# 3310.net
KiCad netlist of a schematic drawn in EAGLE
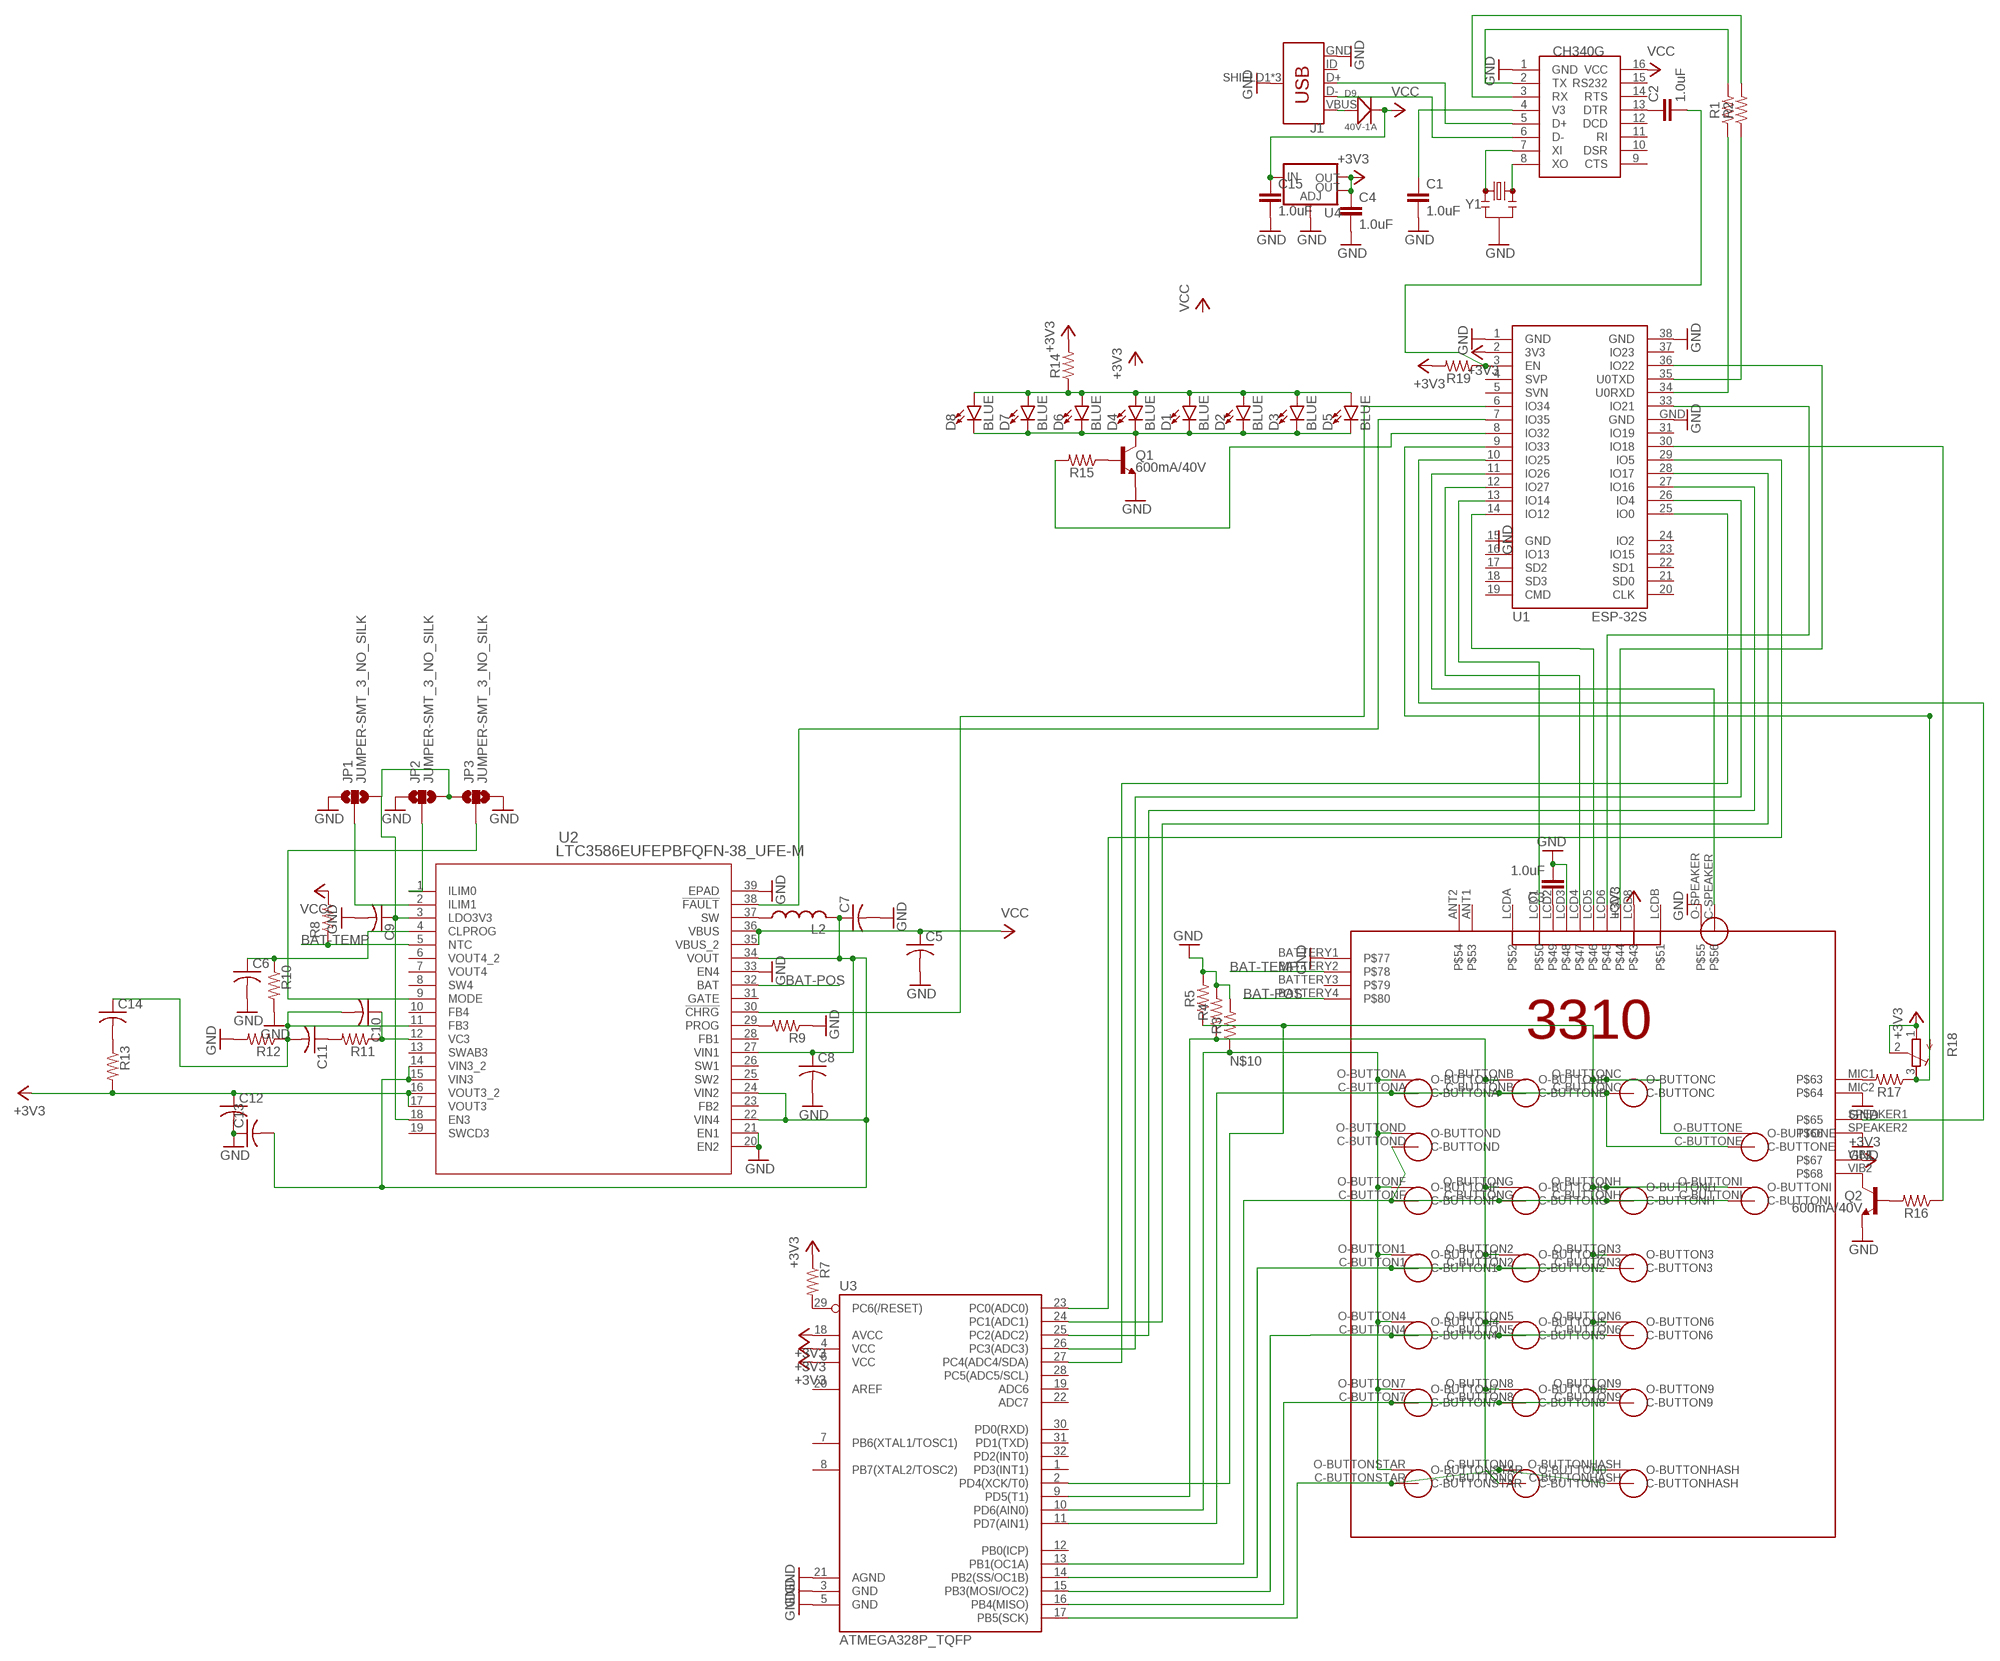
[diagram p0: schematic, sheet 1]

(export (version "E")
  (design (tool "Eeschema 10.0.6"))
  (components
    (comp (ref "C1")
      (value "1.0uF")
      (footprint "eagle-import:0805")
      (libsource (lib "eagle-import") (part "1.0UF-0805-25V-10%"))
    )
    (comp (ref "C2")
      (value "1.0uF")
      (footprint "eagle-import:0805")
      (libsource (lib "eagle-import") (part "1.0UF-0805-25V-10%"))
    )
    (comp (ref "C3")
      (value "1.0uF")
      (footprint "eagle-import:0805")
      (libsource (lib "eagle-import") (part "1.0UF-0805-25V-10%"))
    )
    (comp (ref "C4")
      (value "1.0uF")
      (footprint "eagle-import:0805")
      (libsource (lib "eagle-import") (part "1.0UF-0805-25V-10%"))
    )
    (comp (ref "C5")
      (value "C-USC0805K")
      (footprint "eagle-import:C0805K")
      (libsource (lib "eagle-import") (part "C-USC0805K"))
    )
    (comp (ref "C6")
      (value "C-USC0805K")
      (footprint "eagle-import:C0805K")
      (libsource (lib "eagle-import") (part "C-USC0805K"))
    )
    (comp (ref "C7")
      (value "C-USC0805K")
      (footprint "eagle-import:C0805K")
      (libsource (lib "eagle-import") (part "C-USC0805K"))
    )
    (comp (ref "C8")
      (value "C-USC0805K")
      (footprint "eagle-import:C0805K")
      (libsource (lib "eagle-import") (part "C-USC0805K"))
    )
    (comp (ref "C9")
      (value "C-USC0805K")
      (footprint "eagle-import:C0805K")
      (libsource (lib "eagle-import") (part "C-USC0805K"))
    )
    (comp (ref "C10")
      (value "C-USC0805K")
      (footprint "eagle-import:C0805K")
      (libsource (lib "eagle-import") (part "C-USC0805K"))
    )
    (comp (ref "C11")
      (value "C-USC0805K")
      (footprint "eagle-import:C0805K")
      (libsource (lib "eagle-import") (part "C-USC0805K"))
    )
    (comp (ref "C12")
      (value "C-USC0805K")
      (footprint "eagle-import:C0805K")
      (libsource (lib "eagle-import") (part "C-USC0805K"))
    )
    (comp (ref "C13")
      (value "C-USC0805K")
      (footprint "eagle-import:C0805K")
      (libsource (lib "eagle-import") (part "C-USC0805K"))
    )
    (comp (ref "C14")
      (value "C-USC0805K")
      (footprint "eagle-import:C0805K")
      (libsource (lib "eagle-import") (part "C-USC0805K"))
    )
    (comp (ref "C15")
      (value "1.0uF")
      (footprint "eagle-import:0805")
      (libsource (lib "eagle-import") (part "1.0UF-0805-25V-10%"))
    )
    (comp (ref "D1")
      (value "BLUE")
      (footprint "eagle-import:LED-1206")
      (libsource (lib "eagle-import") (part "LED-BLUE1206"))
    )
    (comp (ref "D2")
      (value "BLUE")
      (footprint "eagle-import:LED-1206")
      (libsource (lib "eagle-import") (part "LED-BLUE1206"))
    )
    (comp (ref "D3")
      (value "BLUE")
      (footprint "eagle-import:LED-1206")
      (libsource (lib "eagle-import") (part "LED-BLUE1206"))
    )
    (comp (ref "D4")
      (value "BLUE")
      (footprint "eagle-import:LED-1206")
      (libsource (lib "eagle-import") (part "LED-BLUE1206"))
    )
    (comp (ref "D5")
      (value "BLUE")
      (footprint "eagle-import:LED-1206")
      (libsource (lib "eagle-import") (part "LED-BLUE1206"))
    )
    (comp (ref "D6")
      (value "BLUE")
      (footprint "eagle-import:LED-1206")
      (libsource (lib "eagle-import") (part "LED-BLUE1206"))
    )
    (comp (ref "D7")
      (value "BLUE")
      (footprint "eagle-import:LED-1206")
      (libsource (lib "eagle-import") (part "LED-BLUE1206"))
    )
    (comp (ref "D8")
      (value "BLUE")
      (footprint "eagle-import:LED-1206")
      (libsource (lib "eagle-import") (part "LED-BLUE1206"))
    )
    (comp (ref "D9")
      (value "40V-1A")
      (footprint "eagle-import:DO-214AC")
      (fields (field (name "MPN") "1N5819"))
      (libsource (lib "eagle-import") (part "SMD-DIODE-SCHOTTKY-40V-1A(DO-214AC)"))
    )
    (comp (ref "J1")
      (value "USB_MICRO-BREDUCED_PASTE")
      (footprint "eagle-import:USB-B-MICRO-SMD_RED_PASTE")
      (libsource (lib "eagle-import") (part "USB_MICRO-BREDUCED_PASTE"))
    )
    (comp (ref "JP1")
      (value "JUMPER-SMT_3_NO_SILK")
      (footprint "eagle-import:SMT-JUMPER_3_NO_SILK")
      (libsource (lib "eagle-import") (part "JUMPER-SMT_3_NO_SILK"))
    )
    (comp (ref "JP2")
      (value "JUMPER-SMT_3_NO_SILK")
      (footprint "eagle-import:SMT-JUMPER_3_NO_SILK")
      (libsource (lib "eagle-import") (part "JUMPER-SMT_3_NO_SILK"))
    )
    (comp (ref "JP3")
      (value "JUMPER-SMT_3_NO_SILK")
      (footprint "eagle-import:SMT-JUMPER_3_NO_SILK")
      (libsource (lib "eagle-import") (part "JUMPER-SMT_3_NO_SILK"))
    )
    (comp (ref "L2")
      (value "L-USL3216C")
      (footprint "eagle-import:L3216C")
      (libsource (lib "eagle-import") (part "L-USL3216C"))
    )
    (comp (ref "Q1")
      (value "600mA/40V")
      (footprint "eagle-import:SOT23-3")
      (libsource (lib "eagle-import") (part "TRANS_NPN-MMBT2222AL"))
    )
    (comp (ref "Q2")
      (value "600mA/40V")
      (footprint "eagle-import:SOT23-3")
      (libsource (lib "eagle-import") (part "TRANS_NPN-MMBT2222AL"))
    )
    (comp (ref "R1")
      (value "RESISTOR0805")
      (footprint "eagle-import:0805")
      (libsource (lib "eagle-import") (part "RESISTOR0805"))
    )
    (comp (ref "R2")
      (value "RESISTOR0805")
      (footprint "eagle-import:0805")
      (libsource (lib "eagle-import") (part "RESISTOR0805"))
    )
    (comp (ref "R3")
      (value "RESISTOR0805")
      (footprint "eagle-import:0805")
      (libsource (lib "eagle-import") (part "RESISTOR0805"))
    )
    (comp (ref "R4")
      (value "RESISTOR0805")
      (footprint "eagle-import:0805")
      (libsource (lib "eagle-import") (part "RESISTOR0805"))
    )
    (comp (ref "R5")
      (value "RESISTOR0805")
      (footprint "eagle-import:0805")
      (libsource (lib "eagle-import") (part "RESISTOR0805"))
    )
    (comp (ref "R7")
      (value "R-US_R0805")
      (footprint "eagle-import:R0805")
      (libsource (lib "eagle-import") (part "R-US_R0805"))
    )
    (comp (ref "R8")
      (value "R-US_R0805")
      (footprint "eagle-import:R0805")
      (libsource (lib "eagle-import") (part "R-US_R0805"))
    )
    (comp (ref "R9")
      (value "R-US_R0805")
      (footprint "eagle-import:R0805")
      (libsource (lib "eagle-import") (part "R-US_R0805"))
    )
    (comp (ref "R10")
      (value "R-US_R0805")
      (footprint "eagle-import:R0805")
      (libsource (lib "eagle-import") (part "R-US_R0805"))
    )
    (comp (ref "R11")
      (value "R-US_R0805")
      (footprint "eagle-import:R0805")
      (libsource (lib "eagle-import") (part "R-US_R0805"))
    )
    (comp (ref "R12")
      (value "R-US_R0805")
      (footprint "eagle-import:R0805")
      (libsource (lib "eagle-import") (part "R-US_R0805"))
    )
    (comp (ref "R13")
      (value "R-US_R0805")
      (footprint "eagle-import:R0805")
      (libsource (lib "eagle-import") (part "R-US_R0805"))
    )
    (comp (ref "R14")
      (value "RESISTOR0805")
      (footprint "eagle-import:0805")
      (libsource (lib "eagle-import") (part "RESISTOR0805"))
    )
    (comp (ref "R15")
      (value "RESISTOR0805")
      (footprint "eagle-import:0805")
      (libsource (lib "eagle-import") (part "RESISTOR0805"))
    )
    (comp (ref "R16")
      (value "RESISTOR0805")
      (footprint "eagle-import:0805")
      (libsource (lib "eagle-import") (part "RESISTOR0805"))
    )
    (comp (ref "R17")
      (value "RESISTOR0805")
      (footprint "eagle-import:0805")
      (libsource (lib "eagle-import") (part "RESISTOR0805"))
    )
    (comp (ref "R18")
      (value "R-TRIMM3103")
      (footprint "eagle-import:RTRIM3103")
      (libsource (lib "eagle-import") (part "R-TRIMM3103"))
    )
    (comp (ref "R19")
      (value "RESISTOR0805")
      (footprint "eagle-import:0805")
      (libsource (lib "eagle-import") (part "RESISTOR0805"))
    )
    (comp (ref "U$1")
      (value "3310NOJACKANDSIM")
      (footprint "eagle-import:3310NOJACKANDSIM")
      (libsource (lib "eagle-import") (part "3310NOJACKANDSIM"))
    )
    (comp (ref "U$2")
      (value "CH340G")
      (footprint "eagle-import:SOIC16")
      (libsource (lib "eagle-import") (part "CH340G"))
    )
    (comp (ref "U1")
      (value "ESP-32S")
      (footprint "eagle-import:ESP-32S")
      (libsource (lib "eagle-import") (part "ESP-32S"))
    )
    (comp (ref "U2")
      (value "LTC3586EUFEPBFQFN-38_UFE-M")
      (footprint "eagle-import:QFN-38_UFE-M")
      (fields (field (name "MANUFACTURER_PART_NUMBER") "LTC3586EUFE#PBF"))
      (libsource (lib "eagle-import") (part "LTC3586EUFEPBFQFN-38_UFE-M"))
    )
    (comp (ref "U3")
      (value "ATMEGA328P_TQFP")
      (footprint "eagle-import:TQFP32-08")
      (libsource (lib "eagle-import") (part "ATMEGA328P_TQFP"))
    )
    (comp (ref "U4")
      (value "V_REG_LM1117SOT223")
      (footprint "eagle-import:SOT223")
      (libsource (lib "eagle-import") (part "V_REG_LM1117SOT223"))
    )
    (comp (ref "Y1")
      (value "RESONATORSMD-3.2X1.3")
      (footprint "eagle-import:RESONATOR-SMD-3.2X1.3")
      (libsource (lib "eagle-import") (part "RESONATORSMD-3.2X1.3"))
    )
  )
  (nets
    (net (code "1") (name "+3V3") (class "Default")
      (node (ref "C12") (pin "1") (pinfunction "1_1") (pintype "passive"))
      (node (ref "C4") (pin "1") (pinfunction "1_1") (pintype "passive"))
      (node (ref "R13") (pin "2") (pinfunction "2_2") (pintype "passive"))
      (node (ref "R14") (pin "2") (pinfunction "2_2") (pintype "passive"))
      (node (ref "R18") (pin "1") (pinfunction "A_1") (pintype "passive"))
      (node (ref "R18") (pin "2") (pinfunction "S_2") (pintype "passive"))
      (node (ref "R19") (pin "2") (pinfunction "2_2") (pintype "passive"))
      (node (ref "R7") (pin "1") (pinfunction "1_1") (pintype "passive"))
      (node (ref "U$1") (pin "LCD8") (pinfunction "P$43_LCD8") (pintype "bidirectional"))
      (node (ref "U$1") (pin "VIB1") (pinfunction "P$67_VIB1") (pintype "bidirectional"))
      (node (ref "U1") (pin "2") (pinfunction "3V3_2") (pintype "power_in"))
      (node (ref "U2") (pin "16") (pinfunction "VOUT3_2_16") (pintype "output"))
      (node (ref "U2") (pin "17") (pinfunction "VOUT3_17") (pintype "output"))
      (node (ref "U3") (pin "18") (pinfunction "AVCC_18") (pintype "bidirectional"))
      (node (ref "U3") (pin "4") (pinfunction "VCC_4") (pintype "bidirectional"))
      (node (ref "U3") (pin "6") (pinfunction "VCC_6") (pintype "bidirectional"))
      (node (ref "U4") (pin "2") (pinfunction "OUT_2") (pintype "output"))
      (node (ref "U4") (pin "4") (pinfunction "OUT_4") (pintype "output"))
    )
    (net (code "2") (name "/BAT-POS") (class "Default")
      (node (ref "U$1") (pin "BATTERY4") (pinfunction "P$80_BATTERY4") (pintype "bidirectional"))
      (node (ref "U2") (pin "32") (pinfunction "BAT_32") (pintype "passive"))
    )
    (net (code "3") (name "/BAT-TEMP") (class "Default")
      (node (ref "R8") (pin "1") (pinfunction "1_1") (pintype "passive"))
      (node (ref "U$1") (pin "BATTERY2") (pinfunction "P$78_BATTERY2") (pintype "bidirectional"))
      (node (ref "U2") (pin "5") (pinfunction "NTC_5") (pintype "input"))
    )
    (net (code "4") (name "/N$10") (class "Default")
      (node (ref "R3") (pin "1") (pinfunction "1_1") (pintype "passive"))
      (node (ref "U$1") (pin "O-BUTTON1") (pinfunction "O-BUTTON1_O-BUTTON1") (pintype "bidirectional"))
      (node (ref "U$1") (pin "O-BUTTON4") (pinfunction "O-BUTTON4_O-BUTTON4") (pintype "bidirectional"))
      (node (ref "U$1") (pin "O-BUTTON7") (pinfunction "O-BUTTON7_O-BUTTON7") (pintype "bidirectional"))
      (node (ref "U$1") (pin "O-BUTTONA") (pinfunction "O-BUTTONA_O-BUTTONA") (pintype "bidirectional"))
      (node (ref "U$1") (pin "O-BUTTOND") (pinfunction "O-BUTTOND_O-BUTTOND") (pintype "bidirectional"))
      (node (ref "U$1") (pin "O-BUTTONF") (pinfunction "O-BUTTONF_O-BUTTONF") (pintype "bidirectional"))
      (node (ref "U$1") (pin "O-BUTTONSTAR") (pinfunction "O-BUTTONSTAR_O-BUTTONSTAR") (pintype "bidirectional"))
      (node (ref "U3") (pin "10") (pinfunction "PD6(AIN0)_10") (pintype "bidirectional"))
    )
    (net (code "5") (name "GND") (class "Default")
      (node (ref "C1") (pin "2") (pinfunction "2_2") (pintype "passive"))
      (node (ref "C12") (pin "2") (pinfunction "2_2") (pintype "passive"))
      (node (ref "C13") (pin "1") (pinfunction "1_1") (pintype "passive"))
      (node (ref "C15") (pin "2") (pinfunction "2_2") (pintype "passive"))
      (node (ref "C3") (pin "2") (pinfunction "2_2") (pintype "passive"))
      (node (ref "C4") (pin "2") (pinfunction "2_2") (pintype "passive"))
      (node (ref "C5") (pin "2") (pinfunction "2_2") (pintype "passive"))
      (node (ref "C6") (pin "2") (pinfunction "2_2") (pintype "passive"))
      (node (ref "C7") (pin "2") (pinfunction "2_2") (pintype "passive"))
      (node (ref "C8") (pin "2") (pinfunction "2_2") (pintype "passive"))
      (node (ref "C9") (pin "2") (pinfunction "2_2") (pintype "passive"))
      (node (ref "J1") (pin "GND") (pinfunction "GND_GND") (pintype "power_in"))
      (node (ref "J1") (pin "SHIELD1") (pinfunction "SHIELD_SHIELD1") (pintype "bidirectional"))
      (node (ref "J1") (pin "SHIELD2") (pinfunction "SHIELD_SHIELD2") (pintype "bidirectional"))
      (node (ref "J1") (pin "SHIELD3") (pinfunction "SHIELD_SHIELD3") (pintype "bidirectional"))
      (node (ref "JP1") (pin "1") (pinfunction "1_1") (pintype "passive"))
      (node (ref "JP2") (pin "1") (pinfunction "1_1") (pintype "passive"))
      (node (ref "JP3") (pin "3") (pinfunction "3_3") (pintype "passive"))
      (node (ref "Q1") (pin "2") (pinfunction "E_2") (pintype "passive"))
      (node (ref "Q2") (pin "2") (pinfunction "E_2") (pintype "passive"))
      (node (ref "R10") (pin "2") (pinfunction "2_2") (pintype "passive"))
      (node (ref "R12") (pin "2") (pinfunction "2_2") (pintype "passive"))
      (node (ref "R3") (pin "2") (pinfunction "2_2") (pintype "passive"))
      (node (ref "R4") (pin "2") (pinfunction "2_2") (pintype "passive"))
      (node (ref "R5") (pin "2") (pinfunction "2_2") (pintype "passive"))
      (node (ref "R9") (pin "1") (pinfunction "1_1") (pintype "passive"))
      (node (ref "U$1") (pin "BATTERY1") (pinfunction "P$77_BATTERY1") (pintype "bidirectional"))
      (node (ref "U$1") (pin "LCD3") (pinfunction "P$48_LCD3") (pintype "bidirectional"))
      (node (ref "U$1") (pin "MIC2") (pinfunction "P$64_MIC2") (pintype "bidirectional"))
      (node (ref "U$1") (pin "O-SPEAKER") (pinfunction "P$55_O-SPEAKER") (pintype "bidirectional"))
      (node (ref "U$1") (pin "SPEAKER2") (pinfunction "P$66_SPEAKER2") (pintype "bidirectional"))
      (node (ref "U$2") (pin "1") (pinfunction "GND_1") (pintype "bidirectional"))
      (node (ref "U1") (pin "1") (pinfunction "GND_1") (pintype "power_in"))
      (node (ref "U1") (pin "15") (pinfunction "GND_15") (pintype "power_in"))
      (node (ref "U1") (pin "38") (pinfunction "GND_38") (pintype "power_in"))
      (node (ref "U1") (pin "GND") (pinfunction "GND_GND") (pintype "power_in"))
      (node (ref "U2") (pin "20") (pinfunction "EN2_20") (pintype "input"))
      (node (ref "U2") (pin "21") (pinfunction "EN1_21") (pintype "input"))
      (node (ref "U2") (pin "33") (pinfunction "EN4_33") (pintype "input"))
      (node (ref "U2") (pin "39") (pinfunction "EPAD_39") (pintype "passive"))
      (node (ref "U3") (pin "21") (pinfunction "AGND_21") (pintype "bidirectional"))
      (node (ref "U3") (pin "3") (pinfunction "GND_3") (pintype "bidirectional"))
      (node (ref "U3") (pin "5") (pinfunction "GND_5") (pintype "bidirectional"))
      (node (ref "U4") (pin "1") (pinfunction "ADJ_1") (pintype "input"))
      (node (ref "Y1") (pin "2") (pinfunction "2_2") (pintype "passive"))
    )
    (net (code "6") (name "Net-(C11-Pad1)") (class "Default")
      (node (ref "C11") (pin "1") (pinfunction "1_1") (pintype "passive"))
      (node (ref "R11") (pin "2") (pinfunction "2_2") (pintype "passive"))
    )
    (net (code "7") (name "Net-(C14-Pad2)") (class "Default")
      (node (ref "C14") (pin "2") (pinfunction "2_2") (pintype "passive"))
      (node (ref "R13") (pin "1") (pinfunction "1_1") (pintype "passive"))
    )
    (net (code "8") (name "Net-(D1-PadA)") (class "Default")
      (node (ref "D1") (pin "A") (pinfunction "A_A") (pintype "passive"))
      (node (ref "D2") (pin "A") (pinfunction "A_A") (pintype "passive"))
      (node (ref "D3") (pin "A") (pinfunction "A_A") (pintype "passive"))
      (node (ref "D4") (pin "A") (pinfunction "A_A") (pintype "passive"))
      (node (ref "D5") (pin "A") (pinfunction "A_A") (pintype "passive"))
      (node (ref "D6") (pin "A") (pinfunction "A_A") (pintype "passive"))
      (node (ref "D7") (pin "A") (pinfunction "A_A") (pintype "passive"))
      (node (ref "D8") (pin "A") (pinfunction "A_A") (pintype "passive"))
      (node (ref "R14") (pin "1") (pinfunction "1_1") (pintype "passive"))
    )
    (net (code "9") (name "Net-(D9-+)") (class "Default")
      (node (ref "D9") (pin "1") (pinfunction "+_1") (pintype "passive"))
      (node (ref "J1") (pin "VBUS") (pinfunction "VBUS_VBUS") (pintype "power_in"))
    )
    (net (code "10") (name "Net-(Q1-B)") (class "Default")
      (node (ref "Q1") (pin "1") (pinfunction "B_1") (pintype "passive"))
      (node (ref "R15") (pin "1") (pinfunction "1_1") (pintype "passive"))
    )
    (net (code "11") (name "Net-(Q1-C)") (class "Default")
      (node (ref "D1") (pin "C") (pinfunction "C_C") (pintype "passive"))
      (node (ref "D2") (pin "C") (pinfunction "C_C") (pintype "passive"))
      (node (ref "D3") (pin "C") (pinfunction "C_C") (pintype "passive"))
      (node (ref "D4") (pin "C") (pinfunction "C_C") (pintype "passive"))
      (node (ref "D5") (pin "C") (pinfunction "C_C") (pintype "passive"))
      (node (ref "D6") (pin "C") (pinfunction "C_C") (pintype "passive"))
      (node (ref "D7") (pin "C") (pinfunction "C_C") (pintype "passive"))
      (node (ref "D8") (pin "C") (pinfunction "C_C") (pintype "passive"))
      (node (ref "Q1") (pin "3") (pinfunction "C_3") (pintype "passive"))
    )
    (net (code "12") (name "Net-(Q2-B)") (class "Default")
      (node (ref "Q2") (pin "1") (pinfunction "B_1") (pintype "passive"))
      (node (ref "R16") (pin "2") (pinfunction "2_2") (pintype "passive"))
    )
    (net (code "13") (name "Net-(Q2-C)") (class "Default")
      (node (ref "Q2") (pin "3") (pinfunction "C_3") (pintype "passive"))
      (node (ref "U$1") (pin "VIB2") (pinfunction "P$68_VIB2") (pintype "bidirectional"))
    )
    (net (code "14") (name "Net-(R18-E)") (class "Default")
      (node (ref "R17") (pin "1") (pinfunction "1_1") (pintype "passive"))
      (node (ref "R18") (pin "3") (pinfunction "E_3") (pintype "passive"))
      (node (ref "U1") (pin "9") (pinfunction "IO33_9") (pintype "bidirectional"))
    )
    (net (code "15") (name "Net-(U$1-C-BUTTON0)") (class "Default")
      (node (ref "R4") (pin "1") (pinfunction "1_1") (pintype "passive"))
      (node (ref "U$1") (pin "O-BUTTON0") (pinfunction "C-BUTTON0_O-BUTTON0") (pintype "bidirectional"))
      (node (ref "U$1") (pin "O-BUTTON2") (pinfunction "O-BUTTON2_O-BUTTON2") (pintype "bidirectional"))
      (node (ref "U$1") (pin "O-BUTTON5") (pinfunction "O-BUTTON5_O-BUTTON5") (pintype "bidirectional"))
      (node (ref "U$1") (pin "O-BUTTON8") (pinfunction "O-BUTTON8_O-BUTTON8") (pintype "bidirectional"))
      (node (ref "U$1") (pin "O-BUTTONB") (pinfunction "O-BUTTONB_O-BUTTONB") (pintype "bidirectional"))
      (node (ref "U$1") (pin "O-BUTTONG") (pinfunction "O-BUTTONG_O-BUTTONG") (pintype "bidirectional"))
      (node (ref "U3") (pin "9") (pinfunction "PD5(T1)_9") (pintype "bidirectional"))
    )
    (net (code "16") (name "Net-(U$1-O-BUTTON0)") (class "Default")
      (node (ref "U$1") (pin "C-BUTTON0") (pinfunction "O-BUTTON0_C-BUTTON0") (pintype "bidirectional"))
      (node (ref "U$1") (pin "C-BUTTONHASH") (pinfunction "C-BUTTONHASH_C-BUTTONHASH") (pintype "bidirectional"))
      (node (ref "U$1") (pin "C-BUTTONSTAR") (pinfunction "C-BUTTONSTAR_C-BUTTONSTAR") (pintype "bidirectional"))
      (node (ref "U3") (pin "17") (pinfunction "PB5(SCK)_17") (pintype "bidirectional"))
    )
    (net (code "17") (name "Net-(U$1-P$44)") (class "Default")
      (node (ref "U$1") (pin "LCD7") (pinfunction "P$44_LCD7") (pintype "bidirectional"))
      (node (ref "U1") (pin "36") (pinfunction "IO22_36") (pintype "bidirectional"))
    )
    (net (code "18") (name "Net-(U$1-P$45)") (class "Default")
      (node (ref "U$1") (pin "LCD6") (pinfunction "P$45_LCD6") (pintype "bidirectional"))
      (node (ref "U1") (pin "33") (pinfunction "IO21_33") (pintype "bidirectional"))
    )
    (net (code "19") (name "Net-(U$1-P$46)") (class "Default")
      (node (ref "U$1") (pin "LCD5") (pinfunction "P$46_LCD5") (pintype "bidirectional"))
      (node (ref "U1") (pin "14") (pinfunction "IO12_14") (pintype "bidirectional"))
    )
    (net (code "20") (name "Net-(U$1-P$47)") (class "Default")
      (node (ref "U$1") (pin "LCD4") (pinfunction "P$47_LCD4") (pintype "bidirectional"))
      (node (ref "U1") (pin "12") (pinfunction "IO27_12") (pintype "bidirectional"))
    )
    (net (code "21") (name "Net-(U$1-P$49)") (class "Default")
      (node (ref "C3") (pin "1") (pinfunction "1_1") (pintype "passive"))
      (node (ref "U$1") (pin "LCD2") (pinfunction "P$49_LCD2") (pintype "bidirectional"))
    )
    (net (code "22") (name "Net-(U$1-P$50)") (class "Default")
      (node (ref "U$1") (pin "LCD1") (pinfunction "P$50_LCD1") (pintype "bidirectional"))
      (node (ref "U1") (pin "13") (pinfunction "IO14_13") (pintype "bidirectional"))
    )
    (net (code "23") (name "Net-(U$1-P$56)") (class "Default")
      (node (ref "U$1") (pin "C-SPEAKER") (pinfunction "P$56_C-SPEAKER") (pintype "bidirectional"))
      (node (ref "U1") (pin "11") (pinfunction "IO26_11") (pintype "bidirectional"))
    )
    (net (code "24") (name "Net-(U$1-P$63)") (class "Default")
      (node (ref "R17") (pin "2") (pinfunction "2_2") (pintype "passive"))
      (node (ref "U$1") (pin "MIC1") (pinfunction "P$63_MIC1") (pintype "bidirectional"))
    )
    (net (code "25") (name "Net-(U$1-P$65)") (class "Default")
      (node (ref "U$1") (pin "SPEAKER1") (pinfunction "P$65_SPEAKER1") (pintype "bidirectional"))
      (node (ref "U1") (pin "10") (pinfunction "IO25_10") (pintype "bidirectional"))
    )
    (net (code "26") (name "Net-(U$2-D+)") (class "Default")
      (node (ref "J1") (pin "D+") (pinfunction "D+_D+") (pintype "bidirectional"))
      (node (ref "U$2") (pin "5") (pinfunction "D+_5") (pintype "bidirectional"))
    )
    (net (code "27") (name "Net-(U$2-D-)") (class "Default")
      (node (ref "J1") (pin "D-") (pinfunction "D-_D-") (pintype "bidirectional"))
      (node (ref "U$2") (pin "6") (pinfunction "D-_6") (pintype "bidirectional"))
    )
    (net (code "28") (name "Net-(U$2-DTR)") (class "Default")
      (node (ref "C2") (pin "1") (pinfunction "1_1") (pintype "passive"))
      (node (ref "U$2") (pin "13") (pinfunction "DTR_13") (pintype "bidirectional"))
    )
    (net (code "29") (name "Net-(U$2-RX)") (class "Default")
      (node (ref "R2") (pin "2") (pinfunction "2_2") (pintype "passive"))
      (node (ref "U$2") (pin "3") (pinfunction "RX_3") (pintype "bidirectional"))
    )
    (net (code "30") (name "Net-(U$2-TX)") (class "Default")
      (node (ref "R1") (pin "2") (pinfunction "2_2") (pintype "passive"))
      (node (ref "U$2") (pin "2") (pinfunction "TX_2") (pintype "bidirectional"))
    )
    (net (code "31") (name "Net-(U$2-V3)") (class "Default")
      (node (ref "C1") (pin "1") (pinfunction "1_1") (pintype "passive"))
      (node (ref "U$2") (pin "4") (pinfunction "V3_4") (pintype "bidirectional"))
    )
    (net (code "32") (name "Net-(U$2-XI)") (class "Default")
      (node (ref "U$2") (pin "7") (pinfunction "XI_7") (pintype "bidirectional"))
      (node (ref "Y1") (pin "1") (pinfunction "1_1") (pintype "passive"))
    )
    (net (code "33") (name "Net-(U$2-XO)") (class "Default")
      (node (ref "U$2") (pin "8") (pinfunction "XO_8") (pintype "bidirectional"))
      (node (ref "Y1") (pin "3") (pinfunction "3_3") (pintype "passive"))
    )
    (net (code "34") (name "Net-(U1-EN)") (class "Default")
      (node (ref "C2") (pin "2") (pinfunction "2_2") (pintype "passive"))
      (node (ref "R19") (pin "1") (pinfunction "1_1") (pintype "passive"))
      (node (ref "U1") (pin "3") (pinfunction "EN_3") (pintype "input"))
    )
    (net (code "35") (name "Net-(U1-IO0)") (class "Default")
      (node (ref "U1") (pin "25") (pinfunction "IO0_25") (pintype "bidirectional"))
      (node (ref "U3") (pin "27") (pinfunction "PC4(ADC4/SDA)_27") (pintype "bidirectional"))
    )
    (net (code "36") (name "Net-(U1-IO4)") (class "Default")
      (node (ref "U1") (pin "26") (pinfunction "IO4_26") (pintype "bidirectional"))
      (node (ref "U3") (pin "26") (pinfunction "PC3(ADC3)_26") (pintype "bidirectional"))
    )
    (net (code "37") (name "Net-(U1-IO5)") (class "Default")
      (node (ref "U1") (pin "29") (pinfunction "IO5_29") (pintype "bidirectional"))
      (node (ref "U3") (pin "23") (pinfunction "PC0(ADC0)_23") (pintype "bidirectional"))
    )
    (net (code "38") (name "Net-(U1-IO16)") (class "Default")
      (node (ref "U1") (pin "27") (pinfunction "IO16_27") (pintype "bidirectional"))
      (node (ref "U3") (pin "25") (pinfunction "PC2(ADC2)_25") (pintype "bidirectional"))
    )
    (net (code "39") (name "Net-(U1-IO17)") (class "Default")
      (node (ref "U1") (pin "28") (pinfunction "IO17_28") (pintype "bidirectional"))
      (node (ref "U3") (pin "24") (pinfunction "PC1(ADC1)_24") (pintype "bidirectional"))
    )
    (net (code "40") (name "Net-(U1-IO18)") (class "Default")
      (node (ref "R16") (pin "1") (pinfunction "1_1") (pintype "passive"))
      (node (ref "U1") (pin "30") (pinfunction "IO18_30") (pintype "bidirectional"))
    )
    (net (code "41") (name "Net-(U1-IO32)") (class "Default")
      (node (ref "R15") (pin "2") (pinfunction "2_2") (pintype "passive"))
      (node (ref "U1") (pin "8") (pinfunction "IO32_8") (pintype "bidirectional"))
    )
    (net (code "42") (name "Net-(U1-IO34)") (class "Default")
      (node (ref "U1") (pin "6") (pinfunction "IO34_6") (pintype "bidirectional"))
      (node (ref "U2") (pin "30") (pinfunction "~{CHRG}_30") (pintype "output"))
    )
    (net (code "43") (name "Net-(U1-IO35)") (class "Default")
      (node (ref "U1") (pin "7") (pinfunction "IO35_7") (pintype "bidirectional"))
      (node (ref "U2") (pin "38") (pinfunction "~{FAULT}_38") (pintype "bidirectional"))
    )
    (net (code "44") (name "Net-(U1-U0RXD)") (class "Default")
      (node (ref "R1") (pin "1") (pinfunction "1_1") (pintype "passive"))
      (node (ref "U1") (pin "34") (pinfunction "U0RXD_34") (pintype "bidirectional"))
    )
    (net (code "45") (name "Net-(U1-U0TXD)") (class "Default")
      (node (ref "R2") (pin "1") (pinfunction "1_1") (pintype "passive"))
      (node (ref "U1") (pin "35") (pinfunction "U0TXD_35") (pintype "bidirectional"))
    )
    (net (code "46") (name "Net-(U2-CLPROG)") (class "Default")
      (node (ref "C6") (pin "1") (pinfunction "1_1") (pintype "passive"))
      (node (ref "R10") (pin "1") (pinfunction "1_1") (pintype "passive"))
      (node (ref "U2") (pin "4") (pinfunction "CLPROG_4") (pintype "input"))
    )
    (net (code "47") (name "Net-(U2-EN3)") (class "Default")
      (node (ref "C9") (pin "1") (pinfunction "1_1") (pintype "passive"))
      (node (ref "JP1") (pin "3") (pinfunction "3_3") (pintype "passive"))
      (node (ref "JP2") (pin "3") (pinfunction "3_3") (pintype "passive"))
      (node (ref "JP3") (pin "1") (pinfunction "1_1") (pintype "passive"))
      (node (ref "U2") (pin "18") (pinfunction "EN3_18") (pintype "input"))
      (node (ref "U2") (pin "3") (pinfunction "LDO3V3_3") (pintype "output"))
    )
    (net (code "48") (name "Net-(U2-FB3)") (class "Default")
      (node (ref "C10") (pin "2") (pinfunction "2_2") (pintype "passive"))
      (node (ref "C11") (pin "2") (pinfunction "2_2") (pintype "passive"))
      (node (ref "C14") (pin "1") (pinfunction "1_1") (pintype "passive"))
      (node (ref "R12") (pin "1") (pinfunction "1_1") (pintype "passive"))
      (node (ref "U2") (pin "11") (pinfunction "FB3_11") (pintype "input"))
    )
    (net (code "49") (name "Net-(U2-ILIM0)") (class "Default")
      (node (ref "JP2") (pin "2") (pinfunction "2_2") (pintype "passive"))
      (node (ref "U2") (pin "1") (pinfunction "ILIM0_1") (pintype "input"))
    )
    (net (code "50") (name "Net-(U2-ILIM1)") (class "Default")
      (node (ref "JP1") (pin "2") (pinfunction "2_2") (pintype "passive"))
      (node (ref "U2") (pin "2") (pinfunction "ILIM1_2") (pintype "input"))
    )
    (net (code "51") (name "Net-(U2-MODE)") (class "Default")
      (node (ref "JP3") (pin "2") (pinfunction "2_2") (pintype "passive"))
      (node (ref "U2") (pin "9") (pinfunction "MODE_9") (pintype "input"))
    )
    (net (code "52") (name "Net-(U2-PROG)") (class "Default")
      (node (ref "R9") (pin "2") (pinfunction "2_2") (pintype "passive"))
      (node (ref "U2") (pin "29") (pinfunction "PROG_29") (pintype "passive"))
    )
    (net (code "53") (name "Net-(U2-SW)") (class "Default")
      (node (ref "L2") (pin "1") (pinfunction "1_1") (pintype "passive"))
      (node (ref "U2") (pin "37") (pinfunction "SW_37") (pintype "passive"))
    )
    (net (code "54") (name "Net-(U2-VC3)") (class "Default")
      (node (ref "C10") (pin "1") (pinfunction "1_1") (pintype "passive"))
      (node (ref "R11") (pin "1") (pinfunction "1_1") (pintype "passive"))
      (node (ref "U2") (pin "12") (pinfunction "VC3_12") (pintype "output"))
    )
    (net (code "55") (name "Net-(U2-VIN1)") (class "Default")
      (node (ref "C13") (pin "2") (pinfunction "2_2") (pintype "passive"))
      (node (ref "C7") (pin "1") (pinfunction "1_1") (pintype "passive"))
      (node (ref "C8") (pin "1") (pinfunction "1_1") (pintype "passive"))
      (node (ref "L2") (pin "2") (pinfunction "2_2") (pintype "passive"))
      (node (ref "U2") (pin "14") (pinfunction "VIN3_2_14") (pintype "input"))
      (node (ref "U2") (pin "15") (pinfunction "VIN3_15") (pintype "input"))
      (node (ref "U2") (pin "22") (pinfunction "VIN4_22") (pintype "input"))
      (node (ref "U2") (pin "24") (pinfunction "VIN2_24") (pintype "input"))
      (node (ref "U2") (pin "27") (pinfunction "VIN1_27") (pintype "input"))
      (node (ref "U2") (pin "34") (pinfunction "VOUT_34") (pintype "output"))
    )
    (net (code "56") (name "Net-(U3-PB1(OC1A))") (class "Default")
      (node (ref "U$1") (pin "C-BUTTOND") (pinfunction "C-BUTTOND_C-BUTTOND") (pintype "bidirectional"))
      (node (ref "U$1") (pin "C-BUTTONF") (pinfunction "C-BUTTONF_C-BUTTONF") (pintype "bidirectional"))
      (node (ref "U$1") (pin "C-BUTTONG") (pinfunction "C-BUTTONG_C-BUTTONG") (pintype "bidirectional"))
      (node (ref "U$1") (pin "C-BUTTONH") (pinfunction "C-BUTTONH_C-BUTTONH") (pintype "bidirectional"))
      (node (ref "U$1") (pin "C-BUTTONI") (pinfunction "C-BUTTONI_C-BUTTONI") (pintype "bidirectional"))
      (node (ref "U3") (pin "13") (pinfunction "PB1(OC1A)_13") (pintype "bidirectional"))
    )
    (net (code "57") (name "Net-(U3-PB2(SS{slash}OC1B))") (class "Default")
      (node (ref "U$1") (pin "C-BUTTON1") (pinfunction "C-BUTTON1_C-BUTTON1") (pintype "bidirectional"))
      (node (ref "U$1") (pin "C-BUTTON2") (pinfunction "C-BUTTON2_C-BUTTON2") (pintype "bidirectional"))
      (node (ref "U$1") (pin "C-BUTTON3") (pinfunction "C-BUTTON3_C-BUTTON3") (pintype "bidirectional"))
      (node (ref "U3") (pin "14") (pinfunction "PB2(SS/OC1B)_14") (pintype "bidirectional"))
    )
    (net (code "58") (name "Net-(U3-PB3(MOSI{slash}OC2))") (class "Default")
      (node (ref "U$1") (pin "C-BUTTON4") (pinfunction "C-BUTTON4_C-BUTTON4") (pintype "bidirectional"))
      (node (ref "U$1") (pin "C-BUTTON5") (pinfunction "C-BUTTON5_C-BUTTON5") (pintype "bidirectional"))
      (node (ref "U$1") (pin "C-BUTTON6") (pinfunction "C-BUTTON6_C-BUTTON6") (pintype "bidirectional"))
      (node (ref "U3") (pin "15") (pinfunction "PB3(MOSI/OC2)_15") (pintype "bidirectional"))
    )
    (net (code "59") (name "Net-(U3-PB4(MISO))") (class "Default")
      (node (ref "U$1") (pin "C-BUTTON7") (pinfunction "C-BUTTON7_C-BUTTON7") (pintype "bidirectional"))
      (node (ref "U$1") (pin "C-BUTTON8") (pinfunction "C-BUTTON8_C-BUTTON8") (pintype "bidirectional"))
      (node (ref "U$1") (pin "C-BUTTON9") (pinfunction "C-BUTTON9_C-BUTTON9") (pintype "bidirectional"))
      (node (ref "U3") (pin "16") (pinfunction "PB4(MISO)_16") (pintype "bidirectional"))
    )
    (net (code "60") (name "Net-(U3-PC6({slash}RESET))") (class "Default")
      (node (ref "R7") (pin "2") (pinfunction "2_2") (pintype "passive"))
      (node (ref "U3") (pin "29") (pinfunction "PC6(/RESET)_29") (pintype "bidirectional"))
    )
    (net (code "61") (name "Net-(U3-PD4(XCK{slash}T0))") (class "Default")
      (node (ref "R5") (pin "1") (pinfunction "1_1") (pintype "passive"))
      (node (ref "U$1") (pin "O-BUTTON3") (pinfunction "O-BUTTON3_O-BUTTON3") (pintype "bidirectional"))
      (node (ref "U$1") (pin "O-BUTTON6") (pinfunction "O-BUTTON6_O-BUTTON6") (pintype "bidirectional"))
      (node (ref "U$1") (pin "O-BUTTON9") (pinfunction "O-BUTTON9_O-BUTTON9") (pintype "bidirectional"))
      (node (ref "U$1") (pin "O-BUTTONC") (pinfunction "O-BUTTONC_O-BUTTONC") (pintype "bidirectional"))
      (node (ref "U$1") (pin "O-BUTTONE") (pinfunction "O-BUTTONE_O-BUTTONE") (pintype "bidirectional"))
      (node (ref "U$1") (pin "O-BUTTONH") (pinfunction "O-BUTTONH_O-BUTTONH") (pintype "bidirectional"))
      (node (ref "U$1") (pin "O-BUTTONHASH") (pinfunction "O-BUTTONHASH_O-BUTTONHASH") (pintype "bidirectional"))
      (node (ref "U$1") (pin "O-BUTTONI") (pinfunction "O-BUTTONI_O-BUTTONI") (pintype "bidirectional"))
      (node (ref "U3") (pin "2") (pinfunction "PD4(XCK/T0)_2") (pintype "bidirectional"))
    )
    (net (code "62") (name "Net-(U3-PD7(AIN1))") (class "Default")
      (node (ref "U$1") (pin "C-BUTTONA") (pinfunction "C-BUTTONA_C-BUTTONA") (pintype "bidirectional"))
      (node (ref "U$1") (pin "C-BUTTONB") (pinfunction "C-BUTTONB_C-BUTTONB") (pintype "bidirectional"))
      (node (ref "U$1") (pin "C-BUTTONC") (pinfunction "C-BUTTONC_C-BUTTONC") (pintype "bidirectional"))
      (node (ref "U$1") (pin "C-BUTTONE") (pinfunction "C-BUTTONE_C-BUTTONE") (pintype "bidirectional"))
      (node (ref "U3") (pin "11") (pinfunction "PD7(AIN1)_11") (pintype "bidirectional"))
    )
    (net (code "63") (name "VCC") (class "Default")
      (node (ref "C15") (pin "1") (pinfunction "1_1") (pintype "passive"))
      (node (ref "C5") (pin "1") (pinfunction "1_1") (pintype "passive"))
      (node (ref "D9") (pin "2") (pinfunction "-_2") (pintype "passive"))
      (node (ref "R8") (pin "2") (pinfunction "2_2") (pintype "passive"))
      (node (ref "U$2") (pin "16") (pinfunction "VCC_16") (pintype "bidirectional"))
      (node (ref "U2") (pin "35") (pinfunction "VBUS_2_35") (pintype "input"))
      (node (ref "U2") (pin "36") (pinfunction "VBUS_36") (pintype "input"))
      (node (ref "U4") (pin "3") (pinfunction "IN_3") (pintype "input"))
    )
    (net (code "64") (name "unconnected-(J1-PadID)") (class "Default")
      (node (ref "J1") (pin "ID") (pinfunction "ID_ID") (pintype "bidirectional"))
    )
    (net (code "65") (name "unconnected-(U$1-P$51-PadLCDB)") (class "Default")
      (node (ref "U$1") (pin "LCDB") (pinfunction "P$51_LCDB") (pintype "bidirectional"))
    )
    (net (code "66") (name "unconnected-(U$1-P$52-PadLCDA)") (class "Default")
      (node (ref "U$1") (pin "LCDA") (pinfunction "P$52_LCDA") (pintype "bidirectional"))
    )
    (net (code "67") (name "unconnected-(U$1-P$53-PadANT1)") (class "Default")
      (node (ref "U$1") (pin "ANT1") (pinfunction "P$53_ANT1") (pintype "bidirectional"))
    )
    (net (code "68") (name "unconnected-(U$1-P$54-PadANT2)") (class "Default")
      (node (ref "U$1") (pin "ANT2") (pinfunction "P$54_ANT2") (pintype "bidirectional"))
    )
    (net (code "69") (name "unconnected-(U$1-P$79-PadBATTERY3)") (class "Default")
      (node (ref "U$1") (pin "BATTERY3") (pinfunction "P$79_BATTERY3") (pintype "bidirectional"))
    )
    (net (code "70") (name "unconnected-(U$2-CTS-Pad9)") (class "Default")
      (node (ref "U$2") (pin "9") (pinfunction "CTS_9") (pintype "bidirectional"))
    )
    (net (code "71") (name "unconnected-(U$2-DCD-Pad12)") (class "Default")
      (node (ref "U$2") (pin "12") (pinfunction "DCD_12") (pintype "bidirectional"))
    )
    (net (code "72") (name "unconnected-(U$2-DSR-Pad10)") (class "Default")
      (node (ref "U$2") (pin "10") (pinfunction "DSR_10") (pintype "bidirectional"))
    )
    (net (code "73") (name "unconnected-(U$2-RI-Pad11)") (class "Default")
      (node (ref "U$2") (pin "11") (pinfunction "RI_11") (pintype "bidirectional"))
    )
    (net (code "74") (name "unconnected-(U$2-RS232-Pad15)") (class "Default")
      (node (ref "U$2") (pin "15") (pinfunction "RS232_15") (pintype "bidirectional"))
    )
    (net (code "75") (name "unconnected-(U$2-RTS-Pad14)") (class "Default")
      (node (ref "U$2") (pin "14") (pinfunction "RTS_14") (pintype "bidirectional"))
    )
    (net (code "76") (name "unconnected-(U1-CLK-Pad20)") (class "Default")
      (node (ref "U1") (pin "20") (pinfunction "CLK_20") (pintype "bidirectional"))
    )
    (net (code "77") (name "unconnected-(U1-CMD-Pad19)") (class "Default")
      (node (ref "U1") (pin "19") (pinfunction "CMD_19") (pintype "bidirectional"))
    )
    (net (code "78") (name "unconnected-(U1-IO2-Pad24)") (class "Default")
      (node (ref "U1") (pin "24") (pinfunction "IO2_24") (pintype "bidirectional"))
    )
    (net (code "79") (name "unconnected-(U1-IO13-Pad16)") (class "Default")
      (node (ref "U1") (pin "16") (pinfunction "IO13_16") (pintype "bidirectional"))
    )
    (net (code "80") (name "unconnected-(U1-IO15-Pad23)") (class "Default")
      (node (ref "U1") (pin "23") (pinfunction "IO15_23") (pintype "bidirectional"))
    )
    (net (code "81") (name "unconnected-(U1-IO19-Pad31)") (class "Default")
      (node (ref "U1") (pin "31") (pinfunction "IO19_31") (pintype "bidirectional"))
    )
    (net (code "82") (name "unconnected-(U1-IO23-Pad37)") (class "Default")
      (node (ref "U1") (pin "37") (pinfunction "IO23_37") (pintype "bidirectional"))
    )
    (net (code "83") (name "unconnected-(U1-SD0-Pad21)") (class "Default")
      (node (ref "U1") (pin "21") (pinfunction "SD0_21") (pintype "bidirectional"))
    )
    (net (code "84") (name "unconnected-(U1-SD1-Pad22)") (class "Default")
      (node (ref "U1") (pin "22") (pinfunction "SD1_22") (pintype "bidirectional"))
    )
    (net (code "85") (name "unconnected-(U1-SD2-Pad17)") (class "Default")
      (node (ref "U1") (pin "17") (pinfunction "SD2_17") (pintype "bidirectional"))
    )
    (net (code "86") (name "unconnected-(U1-SD3-Pad18)") (class "Default")
      (node (ref "U1") (pin "18") (pinfunction "SD3_18") (pintype "bidirectional"))
    )
    (net (code "87") (name "unconnected-(U1-SVN-Pad5)") (class "Default")
      (node (ref "U1") (pin "5") (pinfunction "SVN_5") (pintype "bidirectional"))
    )
    (net (code "88") (name "unconnected-(U1-SVP-Pad4)") (class "Default")
      (node (ref "U1") (pin "4") (pinfunction "SVP_4") (pintype "bidirectional"))
    )
    (net (code "89") (name "unconnected-(U2-FB1-Pad28)") (class "Default")
      (node (ref "U2") (pin "28") (pinfunction "FB1_28") (pintype "input"))
    )
    (net (code "90") (name "unconnected-(U2-FB2-Pad23)") (class "Default")
      (node (ref "U2") (pin "23") (pinfunction "FB2_23") (pintype "input"))
    )
    (net (code "91") (name "unconnected-(U2-FB4-Pad10)") (class "Default")
      (node (ref "U2") (pin "10") (pinfunction "FB4_10") (pintype "input"))
    )
    (net (code "92") (name "unconnected-(U2-GATE-Pad31)") (class "Default")
      (node (ref "U2") (pin "31") (pinfunction "GATE_31") (pintype "output"))
    )
    (net (code "93") (name "unconnected-(U2-SW1-Pad26)") (class "Default")
      (node (ref "U2") (pin "26") (pinfunction "SW1_26") (pintype "passive"))
    )
    (net (code "94") (name "unconnected-(U2-SW2-Pad25)") (class "Default")
      (node (ref "U2") (pin "25") (pinfunction "SW2_25") (pintype "passive"))
    )
    (net (code "95") (name "unconnected-(U2-SW4-Pad8)") (class "Default")
      (node (ref "U2") (pin "8") (pinfunction "SW4_8") (pintype "passive"))
    )
    (net (code "96") (name "unconnected-(U2-SWAB3-Pad13)") (class "Default")
      (node (ref "U2") (pin "13") (pinfunction "SWAB3_13") (pintype "passive"))
    )
    (net (code "97") (name "unconnected-(U2-SWCD3-Pad19)") (class "Default")
      (node (ref "U2") (pin "19") (pinfunction "SWCD3_19") (pintype "passive"))
    )
    (net (code "98") (name "unconnected-(U2-VOUT4-Pad7)") (class "Default")
      (node (ref "U2") (pin "7") (pinfunction "VOUT4_7") (pintype "output"))
    )
    (net (code "99") (name "unconnected-(U2-VOUT4_2-Pad6)") (class "Default")
      (node (ref "U2") (pin "6") (pinfunction "VOUT4_2_6") (pintype "output"))
    )
    (net (code "100") (name "unconnected-(U3-ADC6-Pad19)") (class "Default")
      (node (ref "U3") (pin "19") (pinfunction "ADC6_19") (pintype "bidirectional"))
    )
    (net (code "101") (name "unconnected-(U3-ADC7-Pad22)") (class "Default")
      (node (ref "U3") (pin "22") (pinfunction "ADC7_22") (pintype "bidirectional"))
    )
    (net (code "102") (name "unconnected-(U3-AREF-Pad20)") (class "Default")
      (node (ref "U3") (pin "20") (pinfunction "AREF_20") (pintype "bidirectional"))
    )
    (net (code "103") (name "unconnected-(U3-PB0(ICP)-Pad12)") (class "Default")
      (node (ref "U3") (pin "12") (pinfunction "PB0(ICP)_12") (pintype "bidirectional"))
    )
    (net (code "104") (name "unconnected-(U3-PB6(XTAL1{slash}TOSC1)-Pad7)") (class "Default")
      (node (ref "U3") (pin "7") (pinfunction "PB6(XTAL1/TOSC1)_7") (pintype "bidirectional"))
    )
    (net (code "105") (name "unconnected-(U3-PB7(XTAL2{slash}TOSC2)-Pad8)") (class "Default")
      (node (ref "U3") (pin "8") (pinfunction "PB7(XTAL2/TOSC2)_8") (pintype "bidirectional"))
    )
    (net (code "106") (name "unconnected-(U3-PC5(ADC5{slash}SCL)-Pad28)") (class "Default")
      (node (ref "U3") (pin "28") (pinfunction "PC5(ADC5/SCL)_28") (pintype "bidirectional"))
    )
    (net (code "107") (name "unconnected-(U3-PD0(RXD)-Pad30)") (class "Default")
      (node (ref "U3") (pin "30") (pinfunction "PD0(RXD)_30") (pintype "bidirectional"))
    )
    (net (code "108") (name "unconnected-(U3-PD1(TXD)-Pad31)") (class "Default")
      (node (ref "U3") (pin "31") (pinfunction "PD1(TXD)_31") (pintype "bidirectional"))
    )
    (net (code "109") (name "unconnected-(U3-PD2(INT0)-Pad32)") (class "Default")
      (node (ref "U3") (pin "32") (pinfunction "PD2(INT0)_32") (pintype "bidirectional"))
    )
    (net (code "110") (name "unconnected-(U3-PD3(INT1)-Pad1)") (class "Default")
      (node (ref "U3") (pin "1") (pinfunction "PD3(INT1)_1") (pintype "bidirectional"))
    )
  )
)
